# Driver_motor.net
KiCad netlist of a schematic drawn in Altium Designer
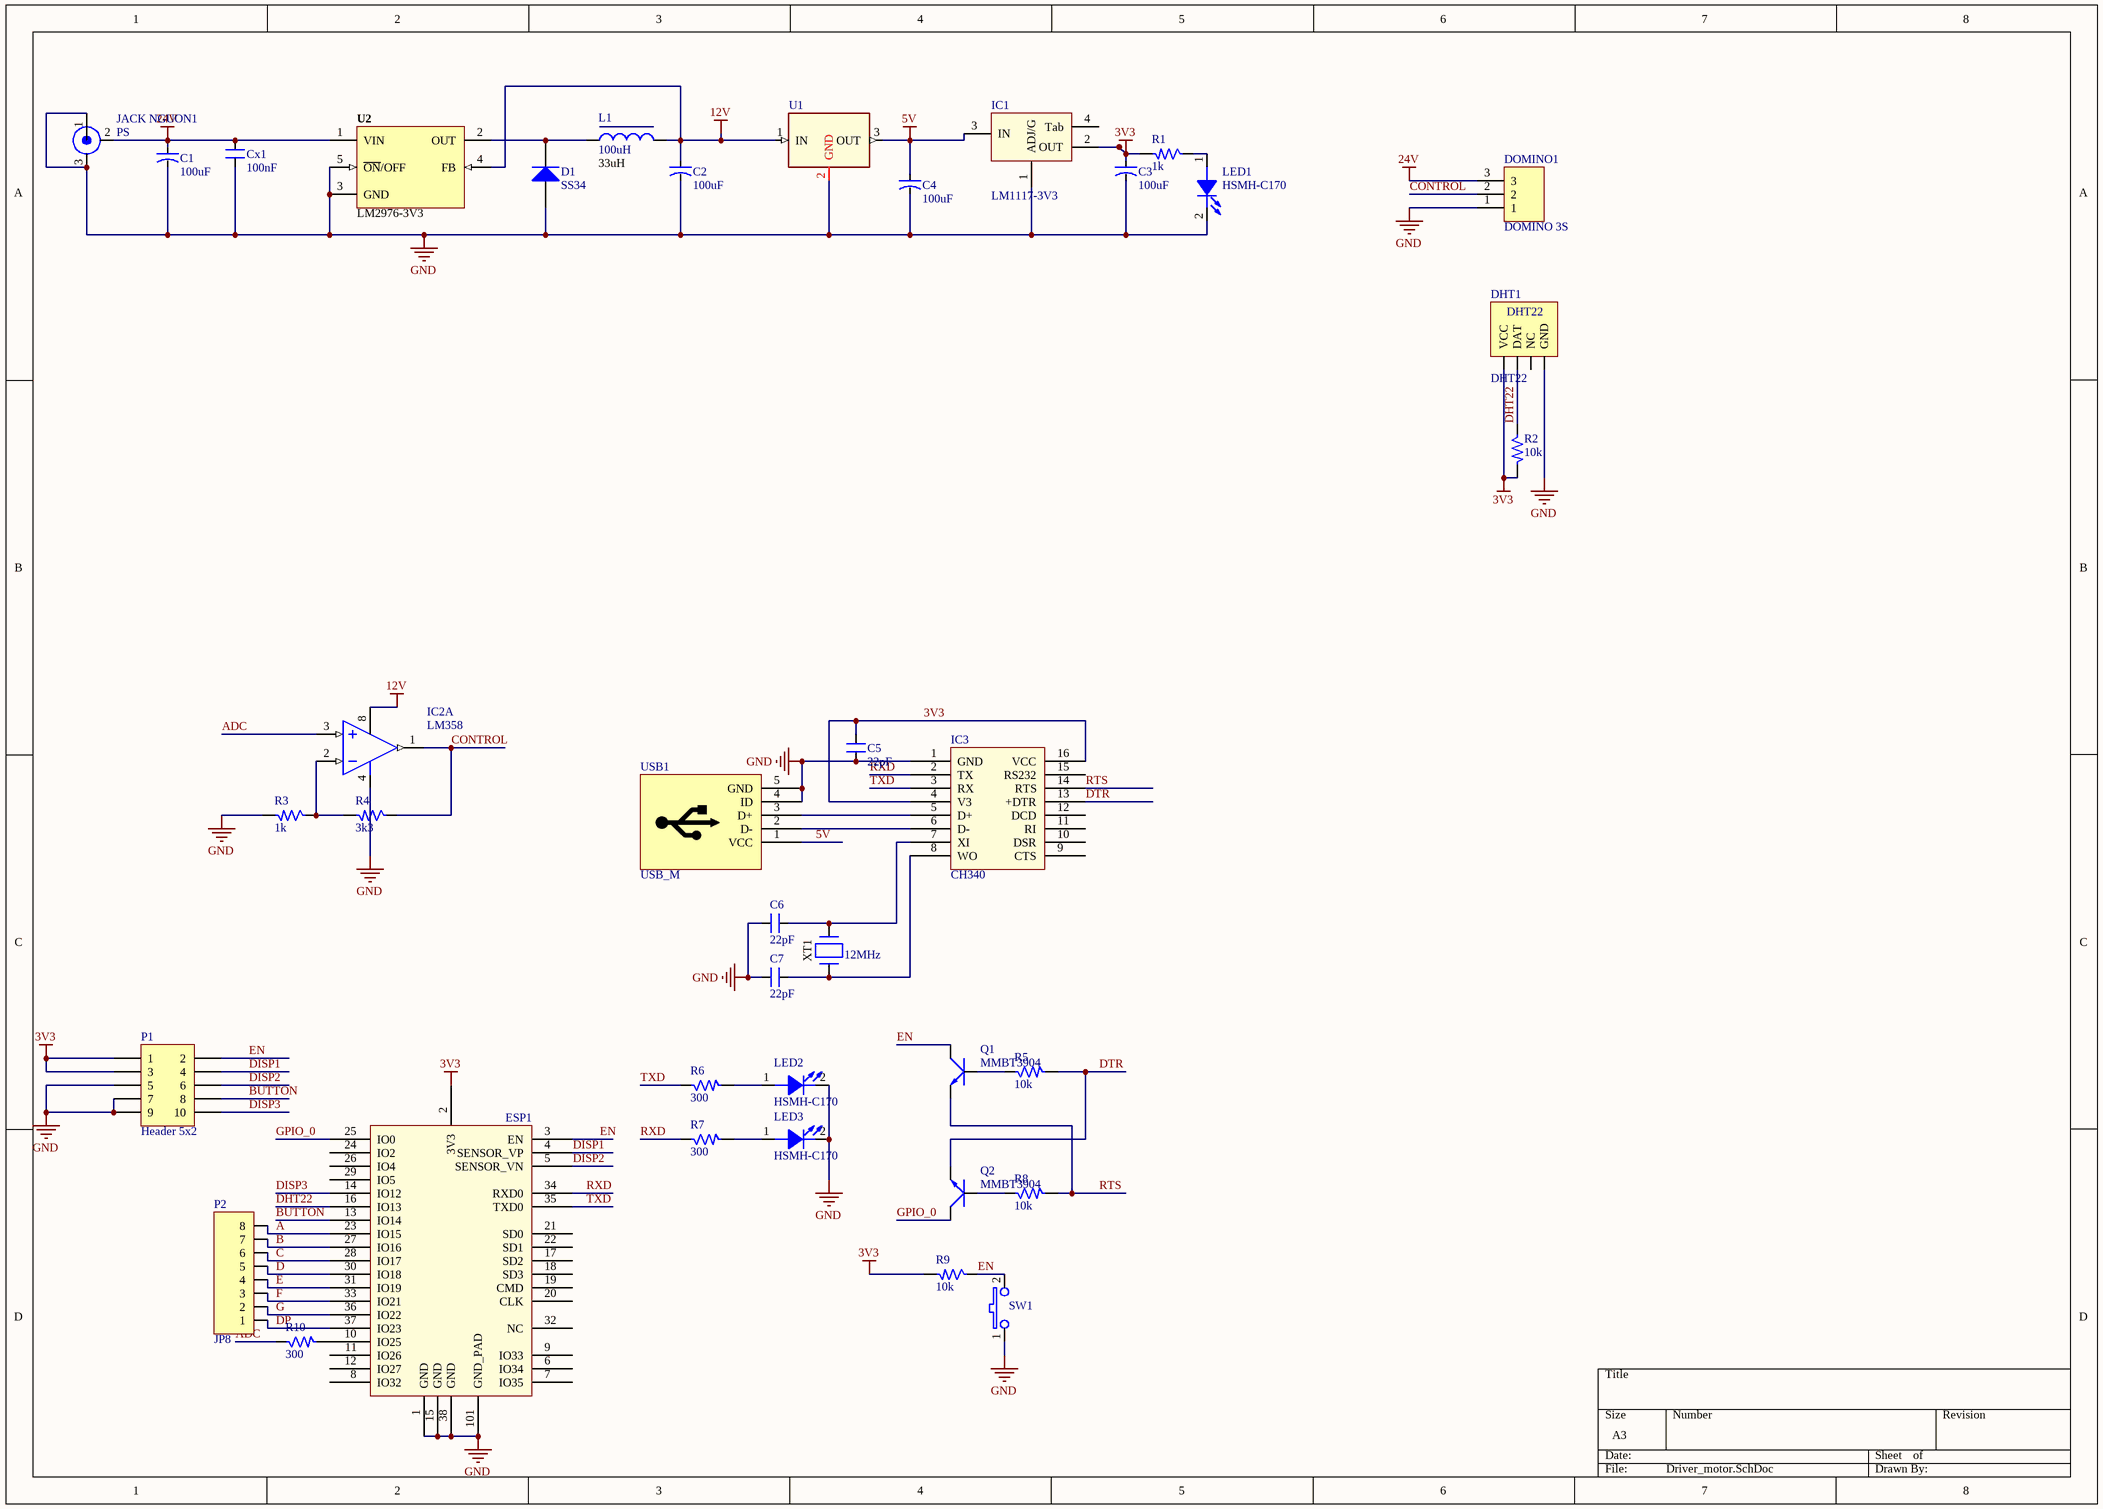
[diagram p0: Driver_motor.SchDoc]

(export (version "E")
  (design (tool "Eeschema 10.0.6"))
  (components
    (comp (ref "C1")
      (value "100uF")
      (footprint "CAP-ALU-SMD-D")
      (description "Polarized Capacitor (Axial)")
      (fields (field (name "PUBLISHER") "Altium Limited"))
      (libsource (lib "LIBRARY") (part "CN-ALU-SMD"))
    )
    (comp (ref "C2")
      (value "100uF")
      (footprint "CAP-ALU-SMD-D")
      (description "Polarized Capacitor (Axial)")
      (fields (field (name "PUBLISHER") "Altium Limited"))
      (libsource (lib "LIBRARY") (part "CN-ALU-SMD"))
    )
    (comp (ref "C3")
      (value "100uF")
      (footprint "CAP-ALU-SMD-D")
      (description "Polarized Capacitor (Axial)")
      (fields (field (name "PUBLISHER") "Altium Limited"))
      (libsource (lib "LIBRARY") (part "CN-ALU-SMD"))
    )
    (comp (ref "C4")
      (value "100uF")
      (footprint "CAP-ALU-SMD-D")
      (description "Polarized Capacitor (Axial)")
      (fields (field (name "PUBLISHER") "Altium Limited"))
      (libsource (lib "LIBRARY") (part "CN-ALU-SMD"))
    )
    (comp (ref "C5")
      (value "22pF")
      (footprint "SM-CAP-0805")
      (description "0,1uF/300V")
      (fields (field (name "DESIGNED BY") "VanDungEvn"))
      (libsource (lib "LIBV.TH") (part "CN"))
    )
    (comp (ref "C6")
      (value "22pF")
      (footprint "SM-CAP-0805")
      (description "0,1uF/300V")
      (fields (field (name "DESIGNED BY") "VanDungEvn"))
      (libsource (lib "LIBV.TH") (part "CN"))
    )
    (comp (ref "C7")
      (value "22pF")
      (footprint "SM-CAP-0805")
      (description "0,1uF/300V")
      (fields (field (name "DESIGNED BY") "VanDungEvn"))
      (libsource (lib "LIBV.TH") (part "CN"))
    )
    (comp (ref "Cx1") (value "100nF") (footprint "CN-SMD-1206") (libsource (lib "LIBRARY") (part "CN")))
    (comp (ref "D1")
      (value "SS34")
      (footprint "DIOT")
      (description "1 Amp General Purpose Rectifier")
      (fields (field (name "PUBLISHER") "Altium Limited"))
      (libsource (lib "thuvienthong") (part "Diode 1N4007"))
    )
    (comp (ref "DHT1")
      (value "DHT22")
      (footprint "DHT22")
      (fields
        (field (name "MANUFACTURER") "Würth Elektronik eiSos GmbH")
        (field (name "PARTNO") "613004143121")
        (field (name "CREATED BY") "Karrer Zheng")
      )
      (libsource (lib "LIBRARY") (part "DHT22"))
    )
    (comp (ref "DOMINO1")
      (value "DOMINO 3S")
      (footprint "DOMINO 3S")
      (libsource (lib "hphonglib") (part "DOMINO 3S"))
    )
    (comp (ref "ESP1")
      (value "ESP32S_Module")
      (footprint "ESP32")
      (description "Esp-32S")
      (libsource (lib "thuvienthong") (part "ESP32S_Module"))
    )
    (comp (ref "IC1")
      (value "LM1117-3V3")
      (footprint "LM1117-3V3-5V")
      (description "3v3")
      (libsource (lib "thuvienthong") (part "LM1117"))
    )
    (comp (ref "IC2")
      (value "LM358")
      (footprint "SO8")
      (description "Low-Power Dual Operational Amplifier")
      (libsource (lib "LIBRARY") (part "LM358"))
    )
    (comp (ref "IC3") (value "CH340") (footprint "ch340 g") (libsource (lib "LIBV.TH") (part "CH340")))
    (comp (ref "JACK NGUON1")
      (value "PS")
      (footprint "jack nguon")
      (description "DC Power Jack, 2.5mm, KLD Series, PCB Mount")
      (libsource (lib "thuvienthong") (part "JACK_DC"))
    )
    (comp (ref "L1")
      (value "100uH")
      (footprint "cuon cam")
      (description "Cuon Cam L")
      (fields (field (name "ALTIUM_VALUE") "33uH") (field (name "PUBLISHER") "Altium Limited"))
      (libsource (lib "thuvienthong") (part "Inductor Ferrite"))
    )
    (comp (ref "LED1")
      (value "HSMH-C170")
      (footprint "LED")
      (description "Typical GaAs SMD LED")
      (fields (field (name "MANUFACTURER") "Lite-On Inc") (field (name "PUBLISHER") "Hoang Nguyen"))
      (libsource (lib "thuvienthong") (part "LED_1"))
    )
    (comp (ref "LED2")
      (value "HSMH-C170")
      (footprint "LED.SMD.GREEN")
      (description "Typical GaAs SMD LED")
      (fields (field (name "MANUFACTURER") "Lite-On Inc") (field (name "PUBLISHER") "Hoang Nguyen"))
      (libsource (lib "hphonglib") (part "LED_1"))
    )
    (comp (ref "LED3")
      (value "HSMH-C170")
      (footprint "LED.SMD.GREEN")
      (description "Typical GaAs SMD LED")
      (fields (field (name "MANUFACTURER") "Lite-On Inc") (field (name "PUBLISHER") "Hoang Nguyen"))
      (libsource (lib "hphonglib") (part "LED_1"))
    )
    (comp (ref "P1")
      (value "Header 5x2")
      (footprint "Header 5x2")
      (description "Header, 10-Pin, 2-Row")
      (fields (field (name "PUBLISHER") "Altium Limited"))
      (libsource (lib "hphonglib") (part "Header 5x2"))
    )
    (comp (ref "P2")
      (value "JP8")
      (footprint "JP8-C1T")
      (description "WR-PHD 2.54 mm Angled Socket Header")
      (fields
        (field (name "MANUFACTURER") "Würth Elektronik eiSos GmbH")
        (field (name "PARTNO") "613008143121")
        (field (name "CREATED BY") "Karrer Zheng")
      )
      (libsource (lib "LIBRARY") (part "JP8"))
    )
    (comp (ref "Q1")
      (value "MMBT3904")
      (footprint "MMBT 3904")
      (libsource (lib "thuvienthong") (part "MMBT3904"))
    )
    (comp (ref "Q2")
      (value "MMBT3904")
      (footprint "MMBT 3904")
      (libsource (lib "thuvienthong") (part "MMBT3904"))
    )
    (comp (ref "R1")
      (value "1k")
      (footprint "SM-RES-0805")
      (description "Resistor 1/4W")
      (libsource (lib "thuvienthong") (part "R_1"))
    )
    (comp (ref "R2")
      (value "10k")
      (footprint "SM-RES-0805")
      (description "Resistor 1/4W")
      (libsource (lib "thuvienthong") (part "R_1"))
    )
    (comp (ref "R3")
      (value "1k")
      (footprint "SM-RES-0805")
      (description "Resistor 1/4W")
      (libsource (lib "thuvienthong") (part "R_1"))
    )
    (comp (ref "R4")
      (value "3k3")
      (footprint "SM-RES-0805")
      (description "Resistor 1/4W")
      (libsource (lib "thuvienthong") (part "R_1"))
    )
    (comp (ref "R5")
      (value "10k")
      (footprint "SM-RES-0805")
      (description "Resistor 1/4W")
      (libsource (lib "thuvienthong") (part "R_1"))
    )
    (comp (ref "R6")
      (value "300")
      (footprint "SM-RES-0805")
      (description "Resistor 1/4W")
      (libsource (lib "thuvienthong") (part "R_1"))
    )
    (comp (ref "R7")
      (value "300")
      (footprint "SM-RES-0805")
      (description "Resistor 1/4W")
      (libsource (lib "thuvienthong") (part "R_1"))
    )
    (comp (ref "R8")
      (value "10k")
      (footprint "SM-RES-0805")
      (description "Resistor 1/4W")
      (libsource (lib "thuvienthong") (part "R_1"))
    )
    (comp (ref "R9")
      (value "10k")
      (footprint "SM-RES-0805")
      (description "Resistor 1/4W")
      (libsource (lib "thuvienthong") (part "R_1"))
    )
    (comp (ref "R10")
      (value "300")
      (footprint "SM-RES-0805")
      (description "Resistor 1/4W")
      (libsource (lib "thuvienthong") (part "R_1"))
    )
    (comp (ref "SW1")
      (value "PTS635")
      (footprint "BUTTON SMD 2PIN")
      (description "BUTTON SMD 2PIN")
      (fields (field (name "MANUFACTURER") "C&K Components") (field (name "PUBLISHER") "Hoang Nguyen"))
      (libsource (lib "thuvienthong") (part "BUTTON SMD 2PIN"))
    )
    (comp (ref "U1")
      (value "LM78xx")
      (footprint "TO-263")
      (description "Regulator")
      (fields
        (field (name "MANUFACTURER") "Fairchild Semiconductor Corporation")
        (field (name "TOLERANCE") "4 %")
        (field (name "PUBLISHER") "Hoang Nguyen")
      )
      (libsource (lib "hphonglib") (part "LM78xx"))
    )
    (comp (ref "U2") (value "LM2976-3V3") (footprint "TO263") (libsource (lib "LIBRARY") (part "LM2596")))
    (comp (ref "USB1") (value "USB_M") (footprint "micro usb") (libsource (lib "syhaunguyen") (part "USB_M")))
    (comp (ref "XT1")
      (value "12MHz")
      (footprint "Crystal.HC49_N")
      (description "Quarz Crystal")
      (fields (field (name "Comment") "Crystal2") (field (name "PUBLISHER") "Hoang Nguyen"))
      (libsource (lib "hphonglib") (part "Crystal2"))
    )
  )
  (nets
    (net (code "1") (name "/A") (class "Default")
      (node (ref "ESP1") (pin "23") (pinfunction "IO15_23") (pintype "passive"))
      (node (ref "P2") (pin "8") (pinfunction "8_8") (pintype "passive"))
    )
    (net (code "2") (name "/ADC") (class "Default")
      (node (ref "IC2") (pin "3") (pinfunction "IN+_3") (pintype "input"))
      (node (ref "R10") (pin "1") (pinfunction "1_1") (pintype "passive"))
    )
    (net (code "3") (name "/B") (class "Default")
      (node (ref "ESP1") (pin "27") (pinfunction "IO16_27") (pintype "passive"))
      (node (ref "P2") (pin "7") (pinfunction "7_7") (pintype "passive"))
    )
    (net (code "4") (name "/BUTTON") (class "Default")
      (node (ref "ESP1") (pin "13") (pinfunction "IO14_13") (pintype "passive"))
      (node (ref "P1") (pin "8") (pinfunction "8_8") (pintype "passive"))
    )
    (net (code "5") (name "/C") (class "Default")
      (node (ref "ESP1") (pin "28") (pinfunction "IO17_28") (pintype "passive"))
      (node (ref "P2") (pin "6") (pinfunction "6_6") (pintype "passive"))
    )
    (net (code "6") (name "/CONTROL") (class "Default")
      (node (ref "DOMINO1") (pin "2") (pinfunction "2_2") (pintype "passive"))
      (node (ref "IC2") (pin "1") (pinfunction "OUT_1") (pintype "output"))
      (node (ref "R4") (pin "1") (pinfunction "1_1") (pintype "passive"))
    )
    (net (code "7") (name "/D") (class "Default")
      (node (ref "ESP1") (pin "30") (pinfunction "IO18_30") (pintype "passive"))
      (node (ref "P2") (pin "5") (pinfunction "5_5") (pintype "passive"))
    )
    (net (code "8") (name "/DHT22") (class "Default")
      (node (ref "DHT1") (pin "2") (pinfunction "DAT_2") (pintype "passive"))
      (node (ref "ESP1") (pin "16") (pinfunction "IO13_16") (pintype "passive"))
      (node (ref "R2") (pin "1") (pinfunction "1_1") (pintype "passive"))
    )
    (net (code "9") (name "/DISP1") (class "Default")
      (node (ref "ESP1") (pin "4") (pinfunction "SENSOR_VP_4") (pintype "passive"))
      (node (ref "P1") (pin "4") (pinfunction "4_4") (pintype "passive"))
    )
    (net (code "10") (name "/DISP2") (class "Default")
      (node (ref "ESP1") (pin "5") (pinfunction "SENSOR_VN_5") (pintype "passive"))
      (node (ref "P1") (pin "6") (pinfunction "6_6") (pintype "passive"))
    )
    (net (code "11") (name "/DISP3") (class "Default")
      (node (ref "ESP1") (pin "14") (pinfunction "IO12_14") (pintype "passive"))
      (node (ref "P1") (pin "10") (pinfunction "10_10") (pintype "passive"))
    )
    (net (code "12") (name "/DP") (class "Default")
      (node (ref "ESP1") (pin "37") (pinfunction "IO23_37") (pintype "passive"))
      (node (ref "P2") (pin "1") (pinfunction "1_1") (pintype "passive"))
    )
    (net (code "13") (name "/DTR") (class "Default")
      (node (ref "IC3") (pin "13") (pinfunction "+DTR_13") (pintype "passive"))
      (node (ref "Q2") (pin "2") (pinfunction "E_2") (pintype "passive"))
      (node (ref "R5") (pin "2") (pinfunction "2_2") (pintype "passive"))
    )
    (net (code "14") (name "/E") (class "Default")
      (node (ref "ESP1") (pin "31") (pinfunction "IO19_31") (pintype "passive"))
      (node (ref "P2") (pin "4") (pinfunction "4_4") (pintype "passive"))
    )
    (net (code "15") (name "/EN") (class "Default")
      (node (ref "ESP1") (pin "3") (pinfunction "EN_3") (pintype "power_in"))
      (node (ref "P1") (pin "2") (pinfunction "2_2") (pintype "passive"))
      (node (ref "Q1") (pin "3") (pinfunction "C_3") (pintype "passive"))
      (node (ref "R9") (pin "1") (pinfunction "1_1") (pintype "passive"))
      (node (ref "SW1") (pin "2") (pinfunction "2_2") (pintype "passive"))
    )
    (net (code "16") (name "/F") (class "Default")
      (node (ref "ESP1") (pin "33") (pinfunction "IO21_33") (pintype "passive"))
      (node (ref "P2") (pin "3") (pinfunction "3_3") (pintype "passive"))
    )
    (net (code "17") (name "/G") (class "Default")
      (node (ref "ESP1") (pin "36") (pinfunction "IO22_36") (pintype "passive"))
      (node (ref "P2") (pin "2") (pinfunction "2_2") (pintype "passive"))
    )
    (net (code "18") (name "/GPIO_0") (class "Default")
      (node (ref "ESP1") (pin "25") (pinfunction "IO0_25") (pintype "passive"))
      (node (ref "Q2") (pin "3") (pinfunction "C_3") (pintype "passive"))
    )
    (net (code "19") (name "/RTS") (class "Default")
      (node (ref "IC3") (pin "14") (pinfunction "RTS_14") (pintype "passive"))
      (node (ref "Q1") (pin "2") (pinfunction "E_2") (pintype "passive"))
      (node (ref "R8") (pin "2") (pinfunction "2_2") (pintype "passive"))
    )
    (net (code "20") (name "/RXD") (class "Default")
      (node (ref "ESP1") (pin "34") (pinfunction "RXD0_34") (pintype "passive"))
      (node (ref "IC3") (pin "2") (pinfunction "TX_2") (pintype "passive"))
      (node (ref "R7") (pin "1") (pinfunction "1_1") (pintype "passive"))
    )
    (net (code "21") (name "/TXD") (class "Default")
      (node (ref "ESP1") (pin "35") (pinfunction "TXD0_35") (pintype "passive"))
      (node (ref "IC3") (pin "3") (pinfunction "RX_3") (pintype "passive"))
      (node (ref "R6") (pin "1") (pinfunction "1_1") (pintype "passive"))
    )
    (net (code "22") (name "3V3") (class "Default")
      (node (ref "C3") (pin "1") (pinfunction "1_1") (pintype "passive"))
      (node (ref "C5") (pin "2") (pinfunction "2_2") (pintype "passive"))
      (node (ref "DHT1") (pin "1") (pinfunction "VCC_1") (pintype "passive"))
      (node (ref "ESP1") (pin "2") (pinfunction "3V3_2") (pintype "power_in"))
      (node (ref "IC1") (pin "2") (pinfunction "OUT_2") (pintype "passive"))
      (node (ref "IC3") (pin "16") (pinfunction "VCC_16") (pintype "passive"))
      (node (ref "IC3") (pin "4") (pinfunction "V3_4") (pintype "passive"))
      (node (ref "P1") (pin "1") (pinfunction "1_1") (pintype "passive"))
      (node (ref "P1") (pin "3") (pinfunction "3_3") (pintype "passive"))
      (node (ref "R1") (pin "2") (pinfunction "2_2") (pintype "passive"))
      (node (ref "R2") (pin "2") (pinfunction "2_2") (pintype "passive"))
      (node (ref "R9") (pin "2") (pinfunction "2_2") (pintype "passive"))
    )
    (net (code "23") (name "5V") (class "Default")
      (node (ref "C4") (pin "1") (pinfunction "1_1") (pintype "passive"))
      (node (ref "IC1") (pin "3") (pinfunction "IN_3") (pintype "passive"))
      (node (ref "U1") (pin "3") (pinfunction "OUT_3") (pintype "output"))
      (node (ref "USB1") (pin "1") (pinfunction "VCC_1") (pintype "passive"))
    )
    (net (code "24") (name "12V") (class "Default")
      (node (ref "C2") (pin "1") (pinfunction "1_1") (pintype "passive"))
      (node (ref "IC2") (pin "8") (pinfunction "+V_8") (pintype "passive"))
      (node (ref "L1") (pin "2") (pinfunction "2_2") (pintype "passive"))
      (node (ref "U1") (pin "1") (pinfunction "IN_1") (pintype "input"))
      (node (ref "U2") (pin "4") (pinfunction "FB_4") (pintype "input"))
    )
    (net (code "25") (name "24V") (class "Default")
      (node (ref "C1") (pin "1") (pinfunction "1_1") (pintype "passive"))
      (node (ref "Cx1") (pin "2") (pinfunction "2_2") (pintype "passive"))
      (node (ref "DOMINO1") (pin "3") (pinfunction "3_3") (pintype "passive"))
      (node (ref "JACK NGUON1") (pin "2") (pinfunction "SHIELD_2") (pintype "power_in"))
      (node (ref "U2") (pin "1") (pinfunction "VIN_1") (pintype "power_in"))
    )
    (net (code "26") (name "GND") (class "Default")
      (node (ref "C1") (pin "2") (pinfunction "2_2") (pintype "passive"))
      (node (ref "C2") (pin "2") (pinfunction "2_2") (pintype "passive"))
      (node (ref "C3") (pin "2") (pinfunction "2_2") (pintype "passive"))
      (node (ref "C4") (pin "2") (pinfunction "2_2") (pintype "passive"))
      (node (ref "C5") (pin "1") (pinfunction "1_1") (pintype "passive"))
      (node (ref "C6") (pin "1") (pinfunction "1_1") (pintype "passive"))
      (node (ref "C7") (pin "1") (pinfunction "1_1") (pintype "passive"))
      (node (ref "Cx1") (pin "1") (pinfunction "1_1") (pintype "passive"))
      (node (ref "D1") (pin "1") (pinfunction "A_1") (pintype "passive"))
      (node (ref "DHT1") (pin "4") (pinfunction "GND_4") (pintype "passive"))
      (node (ref "DOMINO1") (pin "1") (pinfunction "1_1") (pintype "passive"))
      (node (ref "ESP1") (pin "1") (pinfunction "GND_1") (pintype "power_in"))
      (node (ref "ESP1") (pin "101") (pinfunction "GND_PAD_101") (pintype "power_in"))
      (node (ref "ESP1") (pin "15") (pinfunction "GND_15") (pintype "power_in"))
      (node (ref "ESP1") (pin "38") (pinfunction "GND_38") (pintype "power_in"))
      (node (ref "IC1") (pin "1") (pinfunction "ADJ/G_1") (pintype "passive"))
      (node (ref "IC2") (pin "4") (pinfunction "-V_4") (pintype "passive"))
      (node (ref "IC3") (pin "1") (pinfunction "GND_1") (pintype "passive"))
      (node (ref "JACK NGUON1") (pin "1") (pinfunction "CENTER_1") (pintype "power_in"))
      (node (ref "JACK NGUON1") (pin "3") (pinfunction "SHIELD_3") (pintype "passive"))
      (node (ref "LED1") (pin "2") (pinfunction "K_2") (pintype "passive"))
      (node (ref "LED2") (pin "2") (pinfunction "K_2") (pintype "passive"))
      (node (ref "LED3") (pin "2") (pinfunction "K_2") (pintype "passive"))
      (node (ref "P1") (pin "5") (pinfunction "5_5") (pintype "passive"))
      (node (ref "P1") (pin "7") (pinfunction "7_7") (pintype "passive"))
      (node (ref "P1") (pin "9") (pinfunction "9_9") (pintype "passive"))
      (node (ref "R3") (pin "2") (pinfunction "2_2") (pintype "passive"))
      (node (ref "SW1") (pin "1") (pinfunction "1_1") (pintype "passive"))
      (node (ref "U1") (pin "2") (pinfunction "GND_2") (pintype "power_in"))
      (node (ref "U2") (pin "3") (pinfunction "GND_3") (pintype "power_in"))
      (node (ref "U2") (pin "5") (pinfunction "~{ON}/OFF_5") (pintype "input"))
      (node (ref "USB1") (pin "4") (pinfunction "ID_4") (pintype "passive"))
      (node (ref "USB1") (pin "5") (pinfunction "GND_5") (pintype "passive"))
    )
    (net (code "27") (name "Net-(D1-K)") (class "Default")
      (node (ref "D1") (pin "2") (pinfunction "K_2") (pintype "passive"))
      (node (ref "L1") (pin "1") (pinfunction "1_1") (pintype "passive"))
      (node (ref "U2") (pin "2") (pinfunction "OUT_2") (pintype "power_in"))
    )
    (net (code "28") (name "Net-(ESP1-IO25)") (class "Default")
      (node (ref "ESP1") (pin "10") (pinfunction "IO25_10") (pintype "passive"))
      (node (ref "R10") (pin "2") (pinfunction "2_2") (pintype "passive"))
    )
    (net (code "29") (name "Net-(IC2A-IN-)") (class "Default")
      (node (ref "IC2") (pin "2") (pinfunction "IN-_2") (pintype "input"))
      (node (ref "R3") (pin "1") (pinfunction "1_1") (pintype "passive"))
      (node (ref "R4") (pin "2") (pinfunction "2_2") (pintype "passive"))
    )
    (net (code "30") (name "Net-(IC3-D+)") (class "Default")
      (node (ref "IC3") (pin "5") (pinfunction "D+_5") (pintype "passive"))
      (node (ref "USB1") (pin "3") (pinfunction "D+_3") (pintype "passive"))
    )
    (net (code "31") (name "Net-(IC3-D-)") (class "Default")
      (node (ref "IC3") (pin "6") (pinfunction "D-_6") (pintype "passive"))
      (node (ref "USB1") (pin "2") (pinfunction "D-_2") (pintype "passive"))
    )
    (net (code "32") (name "Net-(IC3-WO)") (class "Default")
      (node (ref "C7") (pin "2") (pinfunction "2_2") (pintype "passive"))
      (node (ref "IC3") (pin "8") (pinfunction "WO_8") (pintype "passive"))
      (node (ref "XT1") (pin "1") (pinfunction "1_1") (pintype "passive"))
    )
    (net (code "33") (name "Net-(IC3-XI)") (class "Default")
      (node (ref "C6") (pin "2") (pinfunction "2_2") (pintype "passive"))
      (node (ref "IC3") (pin "7") (pinfunction "XI_7") (pintype "passive"))
      (node (ref "XT1") (pin "2") (pinfunction "2_2") (pintype "passive"))
    )
    (net (code "34") (name "Net-(LED1-A)") (class "Default")
      (node (ref "LED1") (pin "1") (pinfunction "A_1") (pintype "passive"))
      (node (ref "R1") (pin "1") (pinfunction "1_1") (pintype "passive"))
    )
    (net (code "35") (name "Net-(LED2-A)") (class "Default")
      (node (ref "LED2") (pin "1") (pinfunction "A_1") (pintype "passive"))
      (node (ref "R6") (pin "2") (pinfunction "2_2") (pintype "passive"))
    )
    (net (code "36") (name "Net-(LED3-A)") (class "Default")
      (node (ref "LED3") (pin "1") (pinfunction "A_1") (pintype "passive"))
      (node (ref "R7") (pin "2") (pinfunction "2_2") (pintype "passive"))
    )
    (net (code "37") (name "Net-(Q1-B)") (class "Default")
      (node (ref "Q1") (pin "1") (pinfunction "B_1") (pintype "passive"))
      (node (ref "R5") (pin "1") (pinfunction "1_1") (pintype "passive"))
    )
    (net (code "38") (name "Net-(Q2-B)") (class "Default")
      (node (ref "Q2") (pin "1") (pinfunction "B_1") (pintype "passive"))
      (node (ref "R8") (pin "1") (pinfunction "1_1") (pintype "passive"))
    )
    (net (code "39") (name "unconnected-(DHT1-NC-Pad3)") (class "Default")
      (node (ref "DHT1") (pin "3") (pinfunction "NC_3") (pintype "passive"))
    )
    (net (code "40") (name "unconnected-(ESP1-CLK-Pad20)") (class "Default")
      (node (ref "ESP1") (pin "20") (pinfunction "CLK_20") (pintype "passive"))
    )
    (net (code "41") (name "unconnected-(ESP1-CMD-Pad19)") (class "Default")
      (node (ref "ESP1") (pin "19") (pinfunction "CMD_19") (pintype "passive"))
    )
    (net (code "42") (name "unconnected-(ESP1-IO2-Pad24)") (class "Default")
      (node (ref "ESP1") (pin "24") (pinfunction "IO2_24") (pintype "passive"))
    )
    (net (code "43") (name "unconnected-(ESP1-IO4-Pad26)") (class "Default")
      (node (ref "ESP1") (pin "26") (pinfunction "IO4_26") (pintype "passive"))
    )
    (net (code "44") (name "unconnected-(ESP1-IO5-Pad29)") (class "Default")
      (node (ref "ESP1") (pin "29") (pinfunction "IO5_29") (pintype "passive"))
    )
    (net (code "45") (name "unconnected-(ESP1-IO26-Pad11)") (class "Default")
      (node (ref "ESP1") (pin "11") (pinfunction "IO26_11") (pintype "passive"))
    )
    (net (code "46") (name "unconnected-(ESP1-IO27-Pad12)") (class "Default")
      (node (ref "ESP1") (pin "12") (pinfunction "IO27_12") (pintype "passive"))
    )
    (net (code "47") (name "unconnected-(ESP1-IO32-Pad8)") (class "Default")
      (node (ref "ESP1") (pin "8") (pinfunction "IO32_8") (pintype "passive"))
    )
    (net (code "48") (name "unconnected-(ESP1-IO33-Pad9)") (class "Default")
      (node (ref "ESP1") (pin "9") (pinfunction "IO33_9") (pintype "passive"))
    )
    (net (code "49") (name "unconnected-(ESP1-IO34-Pad6)") (class "Default")
      (node (ref "ESP1") (pin "6") (pinfunction "IO34_6") (pintype "passive"))
    )
    (net (code "50") (name "unconnected-(ESP1-IO35-Pad7)") (class "Default")
      (node (ref "ESP1") (pin "7") (pinfunction "IO35_7") (pintype "passive"))
    )
    (net (code "51") (name "unconnected-(ESP1-NC-Pad32)") (class "Default")
      (node (ref "ESP1") (pin "32") (pinfunction "NC_32") (pintype "passive"))
    )
    (net (code "52") (name "unconnected-(ESP1-SD0-Pad21)") (class "Default")
      (node (ref "ESP1") (pin "21") (pinfunction "SD0_21") (pintype "passive"))
    )
    (net (code "53") (name "unconnected-(ESP1-SD1-Pad22)") (class "Default")
      (node (ref "ESP1") (pin "22") (pinfunction "SD1_22") (pintype "passive"))
    )
    (net (code "54") (name "unconnected-(ESP1-SD2-Pad17)") (class "Default")
      (node (ref "ESP1") (pin "17") (pinfunction "SD2_17") (pintype "passive"))
    )
    (net (code "55") (name "unconnected-(ESP1-SD3-Pad18)") (class "Default")
      (node (ref "ESP1") (pin "18") (pinfunction "SD3_18") (pintype "passive"))
    )
    (net (code "56") (name "unconnected-(IC1-Tab-Pad4)") (class "Default")
      (node (ref "IC1") (pin "4") (pinfunction "Tab_4") (pintype "passive"))
    )
    (net (code "57") (name "unconnected-(IC3-CTS-Pad9)") (class "Default")
      (node (ref "IC3") (pin "9") (pinfunction "CTS_9") (pintype "passive"))
    )
    (net (code "58") (name "unconnected-(IC3-DCD-Pad12)") (class "Default")
      (node (ref "IC3") (pin "12") (pinfunction "DCD_12") (pintype "passive"))
    )
    (net (code "59") (name "unconnected-(IC3-DSR-Pad10)") (class "Default")
      (node (ref "IC3") (pin "10") (pinfunction "DSR_10") (pintype "passive"))
    )
    (net (code "60") (name "unconnected-(IC3-RI-Pad11)") (class "Default")
      (node (ref "IC3") (pin "11") (pinfunction "RI_11") (pintype "passive"))
    )
    (net (code "61") (name "unconnected-(IC3-RS232-Pad15)") (class "Default")
      (node (ref "IC3") (pin "15") (pinfunction "RS232_15") (pintype "passive"))
    )
  )
)
